# CameraConnector.net
KiCad netlist of a schematic drawn in Altium Designer
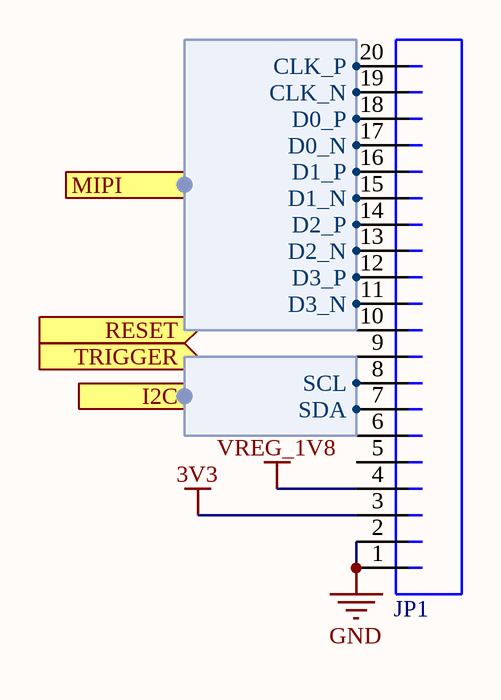
[diagram p0: CameraConnector.SchDoc]

(export (version "E")
  (design (tool "Eeschema 10.0.6"))
  (components
    (comp (ref "JP1")
      (value "JST_JMD_20_HORZ")
      (footprint "JST-JMD-20-SMD-HORZ")
      (fields
        (field (name "MANUFACTURER") "JST Sales America, Inc.")
        (field (name "PARTNUMBER") "20PS-JMDSS-G-1-TF")
      )
      (libsource (lib "Connectors") (part "JST_JMD_20_HORZ"))
    )
  )
  (nets
    (net (code "4") (name "/CLK_N") (class "Default")
      (node (ref "JP1") (pin "19") (pinfunction "19_19") (pintype "passive"))
    )
    (net (code "5") (name "/CLK_P") (class "Default")
      (node (ref "JP1") (pin "20") (pinfunction "20_20") (pintype "passive"))
    )
    (net (code "6") (name "/D0_N") (class "Default")
      (node (ref "JP1") (pin "17") (pinfunction "17_17") (pintype "passive"))
    )
    (net (code "7") (name "/D0_P") (class "Default")
      (node (ref "JP1") (pin "18") (pinfunction "18_18") (pintype "passive"))
    )
    (net (code "8") (name "/D1_N") (class "Default")
      (node (ref "JP1") (pin "15") (pinfunction "15_15") (pintype "passive"))
    )
    (net (code "9") (name "/D1_P") (class "Default")
      (node (ref "JP1") (pin "16") (pinfunction "16_16") (pintype "passive"))
    )
    (net (code "10") (name "/D2_N") (class "Default")
      (node (ref "JP1") (pin "13") (pinfunction "13_13") (pintype "passive"))
    )
    (net (code "11") (name "/D2_P") (class "Default")
      (node (ref "JP1") (pin "14") (pinfunction "14_14") (pintype "passive"))
    )
    (net (code "12") (name "/D3_N") (class "Default")
      (node (ref "JP1") (pin "11") (pinfunction "11_11") (pintype "passive"))
    )
    (net (code "13") (name "/D3_P") (class "Default")
      (node (ref "JP1") (pin "12") (pinfunction "12_12") (pintype "passive"))
    )
    (net (code "15") (name "/RESET") (class "Default")
      (node (ref "JP1") (pin "10") (pinfunction "10_10") (pintype "passive"))
    )
    (net (code "16") (name "/SCL") (class "Default")
      (node (ref "JP1") (pin "8") (pinfunction "8_8") (pintype "passive"))
    )
    (net (code "17") (name "/SDA") (class "Default")
      (node (ref "JP1") (pin "7") (pinfunction "7_7") (pintype "passive"))
    )
    (net (code "18") (name "/{I2C}") (class "Default")
      (node (ref "JP1") (pin "9") (pinfunction "9_9") (pintype "passive"))
    )
    (net (code "20") (name "3V3") (class "Default")
      (node (ref "JP1") (pin "3") (pinfunction "3_3") (pintype "passive"))
    )
    (net (code "21") (name "GND") (class "Default")
      (node (ref "JP1") (pin "1") (pinfunction "1_1") (pintype "passive"))
      (node (ref "JP1") (pin "2") (pinfunction "2_2") (pintype "passive"))
    )
    (net (code "22") (name "VREG_1V8") (class "Default")
      (node (ref "JP1") (pin "4") (pinfunction "4_4") (pintype "passive"))
    )
    (net (code "23") (name "unconnected-(JP1-Pad5)") (class "Default")
      (node (ref "JP1") (pin "5") (pinfunction "5_5") (pintype "passive"))
    )
    (net (code "24") (name "unconnected-(JP1-Pad6)") (class "Default")
      (node (ref "JP1") (pin "6") (pinfunction "6_6") (pintype "passive"))
    )
  )
)
